# 3_cyber60-smk_mcu.net
KiCad netlist of a schematic drawn in Altium Designer
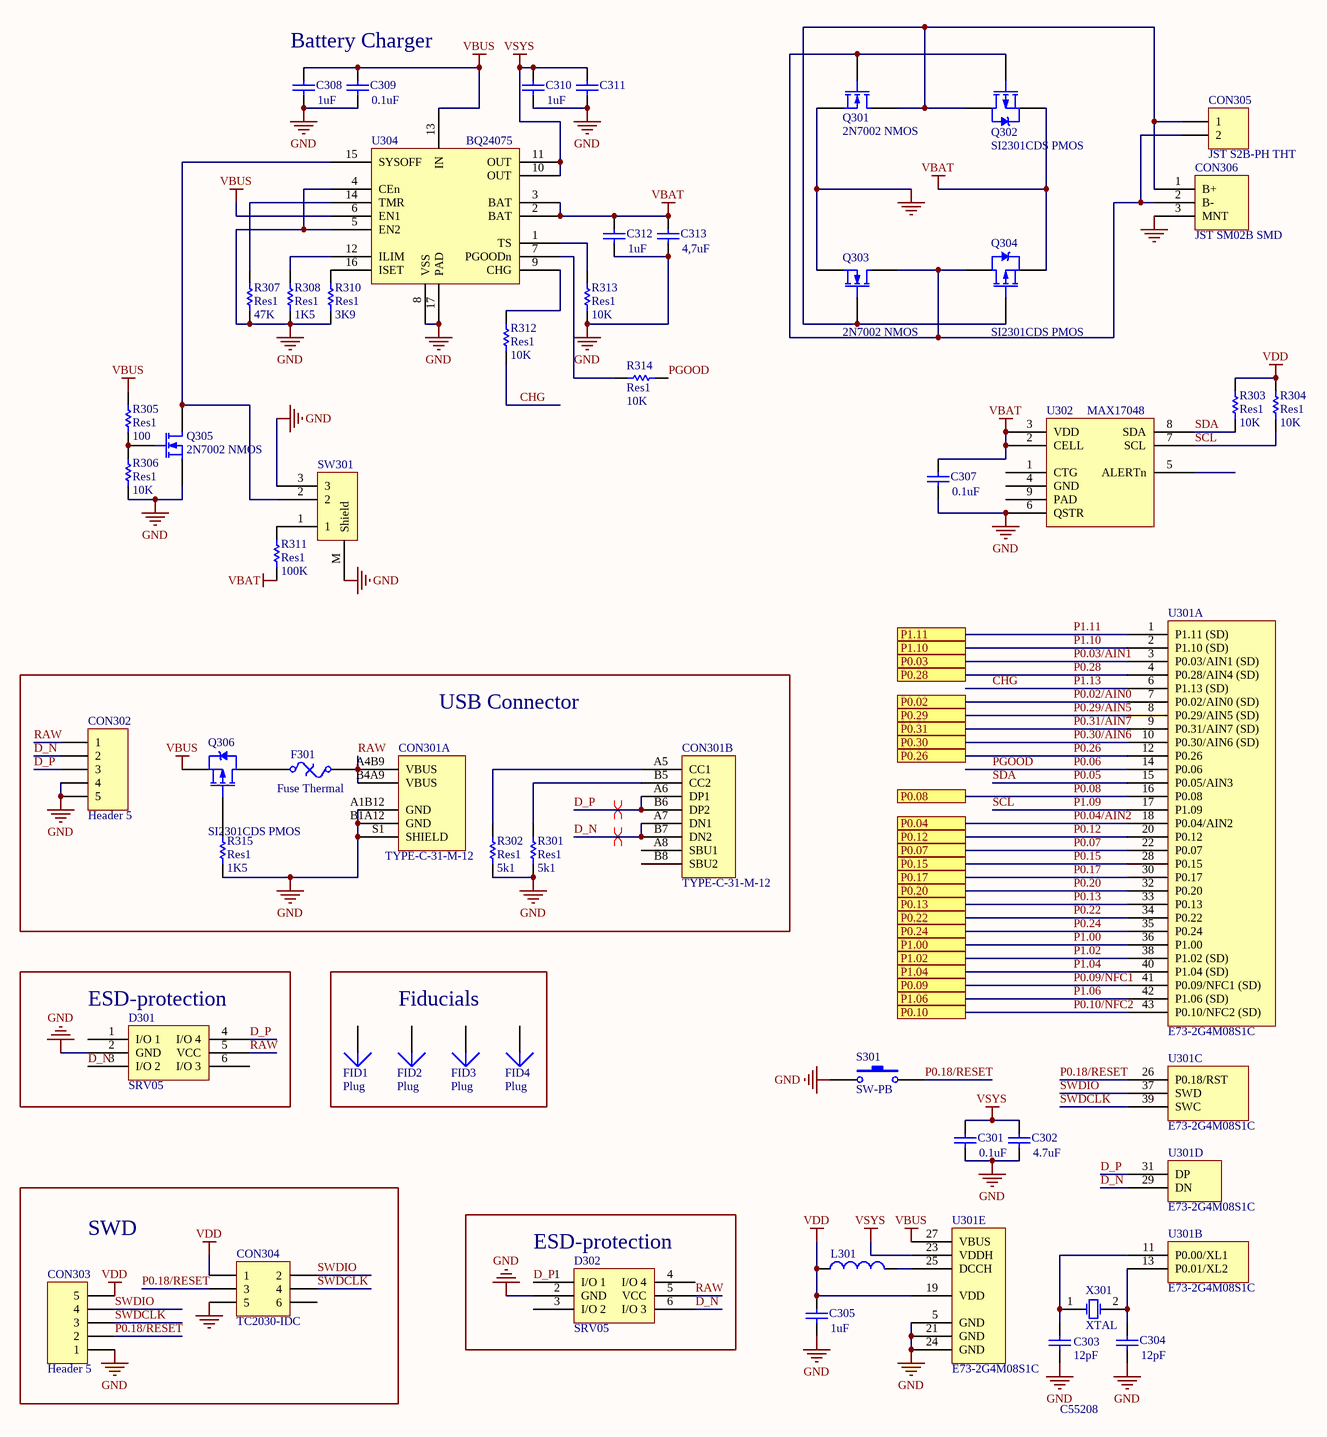
[diagram p0: 3_cyber60-smk_mcu.SchDoc]

(export (version "E")
  (design (tool "Eeschema 10.0.6"))
  (components
    (comp (ref "C301")
      (value "0.1uF")
      (footprint "C0603[1608]")
      (description "Capacitor")
      (fields (field (name "LCSC PART #") "C14663") (field (name "MRF.PART") "CC0603KRX7R9BB104"))
      (libsource (lib "Miscellaneous Devices") (part "Cap"))
    )
    (comp (ref "C302")
      (value "4.7uF")
      (footprint "C0603[1608]")
      (description "Capacitor")
      (fields (field (name "LCSC PART #") "C19666") (field (name "MRF.PART") "CL10A475KO8NNNC"))
      (libsource (lib "Miscellaneous Devices") (part "Cap"))
    )
    (comp (ref "C303")
      (value "12pF")
      (footprint "C0402[1005]")
      (description "Capacitor")
      (fields (field (name "LCSC PART #") "C1547") (field (name "MRF.PART") "0402CG120J500NT"))
      (libsource (lib "Miscellaneous Devices") (part "Cap"))
    )
    (comp (ref "C304")
      (value "12pF")
      (footprint "C0402[1005]")
      (description "Capacitor")
      (fields (field (name "LCSC PART #") "C1547") (field (name "MRF.PART") "0402CG120J500NT"))
      (libsource (lib "Miscellaneous Devices") (part "Cap"))
    )
    (comp (ref "C305")
      (value "1uF")
      (footprint "C0603[1608]")
      (description "Capacitor")
      (fields (field (name "LCSC PART #") "C15849") (field (name "MRF.PART") "CL10A105KB8NNNC"))
      (libsource (lib "Miscellaneous Devices") (part "Cap"))
    )
    (comp (ref "C307")
      (value "0.1uF")
      (footprint "C0603[1608]")
      (description "Capacitor")
      (fields (field (name "LCSC PART #") "C14663") (field (name "MRF.PART") "CC0603KRX7R9BB104"))
      (libsource (lib "Miscellaneous Devices") (part "Cap"))
    )
    (comp (ref "C308")
      (value "1uF")
      (footprint "C0603[1608]")
      (description "Capacitor")
      (fields (field (name "LCSC PART #") "C15849") (field (name "MRF.PART") "CL10A105KB8NNNC"))
      (libsource (lib "Miscellaneous Devices") (part "Cap"))
    )
    (comp (ref "C309")
      (value "0.1uF")
      (footprint "C0603[1608]")
      (description "Capacitor")
      (fields (field (name "LCSC PART #") "C14663") (field (name "MRF.PART") "CC0603KRX7R9BB104"))
      (libsource (lib "Miscellaneous Devices") (part "Cap"))
    )
    (comp (ref "C310")
      (value "1uF")
      (footprint "C0603[1608]")
      (description "Capacitor")
      (fields (field (name "LCSC PART #") "C15849") (field (name "MRF.PART") "CL10A105KB8NNNC"))
      (libsource (lib "Miscellaneous Devices") (part "Cap"))
    )
    (comp (ref "C311")
      (value "~")
      (footprint "C0603[1608]")
      (description "Capacitor")
      (fields (field (name "LCSC PART #") "C19666") (field (name "MRF.PART") "CL10A475KO8NNNC"))
      (libsource (lib "Miscellaneous Devices") (part "Cap"))
    )
    (comp (ref "C312")
      (value "1uF")
      (footprint "C0603[1608]")
      (description "Capacitor")
      (fields (field (name "LCSC PART #") "C15849") (field (name "MRF.PART") "CL10A105KB8NNNC"))
      (libsource (lib "Miscellaneous Devices") (part "Cap"))
    )
    (comp (ref "C313")
      (value "4,7uF")
      (footprint "C0603[1608]")
      (description "Capacitor")
      (fields (field (name "LCSC PART #") "C19666") (field (name "MRF.PART") "CL10A475KO8NNNC"))
      (libsource (lib "Miscellaneous Devices") (part "Cap"))
    )
    (comp (ref "CON301")
      (value "TYPE-C-31-M-12")
      (footprint "TYPE-C-31-M-12")
      (fields (field (name "MFG") "Korean Hroparts Elec") (field (name "LCSC PART #") "C165948"))
      (libsource (lib "Schlib1") (part "TYPE-C-31-M-12"))
    )
    (comp (ref "CON302")
      (value "Header 5")
      (footprint "UDB_COMBO_JST_MOLEX")
      (description "JST for USB daughter board")
      (fields (field (name "MFG") "JST Sales America Inc.") (field (name "LCSC PART #") "C160404"))
      (libsource (lib "") (part "Header 5_1"))
    )
    (comp (ref "CON303")
      (value "Header 5")
      (footprint "HDR1X5")
      (description "Header, 5-Pin")
      (libsource (lib "Miscellaneous Connectors") (part "Header 5"))
    )
    (comp (ref "CON304")
      (value "TC2030-IDC")
      (footprint "TC2030-IDC-NL")
      (description "Header, 3-Pin, Dual row")
      (libsource (lib "Miscellaneous Connectors") (part "Header 3X2"))
    )
    (comp (ref "CON305")
      (value "JST S2B-PH THT")
      (footprint "Keebs:JST S2B-PH-K(LF)(SN)")
      (description "Header, 2-Pin")
      (fields (field (name "LCSC PART #") "C265016") (field (name "MRF.PART") "S2B-PH-K(LF)(SN)"))
      (libsource (lib "Miscellaneous Connectors") (part "Header 2"))
    )
    (comp (ref "CON306")
      (value "JST SM02B SMD")
      (footprint "JST SM02B-SRSS-TB")
      (fields (field (name "LCSC PART #") "C160402") (field (name "MRF.PART") "SM02B-SRSS-TB(LF)(SN)"))
      (libsource (lib "Keebs") (part "JST S2B-PH-SM4-TB"))
    )
    (comp (ref "D301")
      (value "SRV05")
      (footprint "SOT-23-6")
      (fields (field (name "LCSC PART #") "C85364") (field (name "MRF.PART") "SRV05-4-P-T7"))
      (libsource (lib "Keebs") (part "SRV05"))
    )
    (comp (ref "D302")
      (value "SRV05")
      (footprint "SOT-23-6")
      (fields (field (name "LCSC PART #") "C85364") (field (name "MRF.PART") "SRV05-4-P-T7"))
      (libsource (lib "Keebs") (part "SRV05"))
    )
    (comp (ref "F301")
      (value "Fuse Thermal")
      (footprint "C1206[3216]")
      (description "Thermal Fuse")
      (fields (field (name "MFG") "Bel Fuse Inc.") (field (name "LCSC PART #") "C135338"))
      (libsource (lib "Miscellaneous Devices") (part "Fuse Thermal"))
    )
    (comp (ref "FID1")
      (value "Plug")
      (footprint "Fiducial_Nordic")
      (libsource (lib "Miscellaneous Connectors") (part "Plug"))
    )
    (comp (ref "FID2")
      (value "Plug")
      (footprint "Fiducial_Nordic")
      (libsource (lib "Miscellaneous Connectors") (part "Plug"))
    )
    (comp (ref "FID3")
      (value "Plug")
      (footprint "Fiducial_Nordic")
      (libsource (lib "Miscellaneous Connectors") (part "Plug"))
    )
    (comp (ref "FID4")
      (value "Plug")
      (footprint "Fiducial_Nordic")
      (libsource (lib "Miscellaneous Connectors") (part "Plug"))
    )
    (comp (ref "L301")
      (value "Inductor")
      (footprint "L0603[1608]")
      (fields (field (name "LCSC PART #") "C92982") (field (name "MRF.PART") "CBMF1608T100K"))
      (libsource (lib "Simulation Generic Components") (part "Inductor"))
    )
    (comp (ref "Q301")
      (value "2N7002 NMOS")
      (footprint "SOT-23-3")
      (description "N-Channel MOSFET")
      (fields (field (name "LCSC PART #") "C8545") (field (name "MRF.PART") "2N7002"))
      (libsource (lib "Miscellaneous Devices") (part "MOSFET-N"))
    )
    (comp (ref "Q302")
      (value "SI2301CDS PMOS")
      (footprint "SOT-23-3")
      (description "P-Channel Power MOSFET")
      (fields (field (name "MRF.PART") "SI2301CDS-T1-GE3") (field (name "LCSC PART #") "C10487"))
      (libsource (lib "Miscellaneous Devices") (part "PMOS-2"))
    )
    (comp (ref "Q303")
      (value "2N7002 NMOS")
      (footprint "SOT-23-3")
      (description "N-Channel MOSFET")
      (fields (field (name "LCSC PART #") "C8545") (field (name "MRF.PART") "2N7002"))
      (libsource (lib "Miscellaneous Devices") (part "MOSFET-N"))
    )
    (comp (ref "Q304")
      (value "SI2301CDS PMOS")
      (footprint "SOT-23-3")
      (description "P-Channel Power MOSFET")
      (fields (field (name "MRF.PART") "SI2301CDS-T1-GE3") (field (name "LCSC PART #") "C10487"))
      (libsource (lib "Miscellaneous Devices") (part "PMOS-2"))
    )
    (comp (ref "Q305")
      (value "2N7002 NMOS")
      (footprint "SOT-23-3")
      (description "N-Channel MOSFET")
      (fields (field (name "LCSC PART #") "C8545") (field (name "MRF.PART") "2N7002"))
      (libsource (lib "Miscellaneous Devices") (part "MOSFET-N"))
    )
    (comp (ref "Q306")
      (value "SI2301CDS PMOS")
      (footprint "SOT-23-3")
      (description "P-Channel Power MOSFET")
      (fields (field (name "MRF.PART") "SI2301CDS-T1-GE3") (field (name "LCSC PART #") "C10487"))
      (libsource (lib "Miscellaneous Devices") (part "PMOS-2"))
    )
    (comp (ref "R301")
      (value "Res1")
      (footprint "R0603[1608]")
      (description "Resistor")
      (fields
        (field (name "ALTIUM_VALUE") "5k1")
        (field (name "MFG") "Panasonic Electronic Components")
        (field (name "LCSC PART #") "C23186")
      )
      (libsource (lib "Miscellaneous Devices") (part "Res1"))
    )
    (comp (ref "R302")
      (value "Res1")
      (footprint "R0603[1608]")
      (description "Resistor")
      (fields
        (field (name "ALTIUM_VALUE") "5k1")
        (field (name "MFG") "Panasonic Electronic Components")
        (field (name "LCSC PART #") "C23186")
      )
      (libsource (lib "Miscellaneous Devices") (part "Res1"))
    )
    (comp (ref "R303")
      (value "Res1")
      (footprint "R0603[1608]")
      (description "Resistor")
      (fields
        (field (name "ALTIUM_VALUE") "10K")
        (field (name "LCSC PART #") "C25804")
        (field (name "MRF.PART") "0603WAF1002T5E")
      )
      (libsource (lib "Miscellaneous Devices") (part "Res1"))
    )
    (comp (ref "R304")
      (value "Res1")
      (footprint "R0603[1608]")
      (description "Resistor")
      (fields
        (field (name "ALTIUM_VALUE") "10K")
        (field (name "LCSC PART #") "C25804")
        (field (name "MRF.PART") "0603WAF1002T5E")
      )
      (libsource (lib "Miscellaneous Devices") (part "Res1"))
    )
    (comp (ref "R305")
      (value "Res1")
      (footprint "R0603[1608]")
      (description "Resistor")
      (fields
        (field (name "ALTIUM_VALUE") "100")
        (field (name "LCSC PART #") "C22775")
        (field (name "MRF.PART") "0603WAF1000T5E")
      )
      (libsource (lib "Miscellaneous Devices") (part "Res1"))
    )
    (comp (ref "R306")
      (value "Res1")
      (footprint "R0603[1608]")
      (description "Resistor")
      (fields
        (field (name "ALTIUM_VALUE") "10K")
        (field (name "LCSC PART #") "C25804")
        (field (name "MRF.PART") "0603WAF1002T5E")
      )
      (libsource (lib "Miscellaneous Devices") (part "Res1"))
    )
    (comp (ref "R307")
      (value "Res1")
      (footprint "R0603[1608]")
      (description "Resistor")
      (fields
        (field (name "ALTIUM_VALUE") "47K")
        (field (name "LCSC PART #") "C25819")
        (field (name "MRF.PART") "0603WAF4702T5E")
      )
      (libsource (lib "Miscellaneous Devices") (part "Res1"))
    )
    (comp (ref "R308")
      (value "Res1")
      (footprint "R0603[1608]")
      (description "Resistor")
      (fields
        (field (name "ALTIUM_VALUE") "1K5")
        (field (name "LCSC PART #") "C22843")
        (field (name "MRF.PART") "0603WAF1501T5E")
      )
      (libsource (lib "Miscellaneous Devices") (part "Res1"))
    )
    (comp (ref "R310")
      (value "Res1")
      (footprint "R0603[1608]")
      (description "Resistor")
      (fields
        (field (name "ALTIUM_VALUE") "3K9")
        (field (name "LCSC PART #") "C23018")
        (field (name "MRF.PART") "0603WAF3901T5E")
      )
      (libsource (lib "Miscellaneous Devices") (part "Res1"))
    )
    (comp (ref "R311")
      (value "Res1")
      (footprint "R0603[1608]")
      (description "Resistor")
      (fields
        (field (name "ALTIUM_VALUE") "100K")
        (field (name "LCSC PART #") "C25804")
        (field (name "MRF.PART") "0603WAF1002T5E")
      )
      (libsource (lib "Miscellaneous Devices") (part "Res1"))
    )
    (comp (ref "R312")
      (value "Res1")
      (footprint "R0603[1608]")
      (description "Resistor")
      (fields
        (field (name "ALTIUM_VALUE") "10K")
        (field (name "LCSC PART #") "C25804")
        (field (name "MRF.PART") "0603WAF1002T5E")
      )
      (libsource (lib "Miscellaneous Devices") (part "Res1"))
    )
    (comp (ref "R313")
      (value "Res1")
      (footprint "R0603[1608]")
      (description "Resistor")
      (fields
        (field (name "ALTIUM_VALUE") "10K")
        (field (name "LCSC PART #") "C25804")
        (field (name "MRF.PART") "0603WAF1002T5E")
      )
      (libsource (lib "Miscellaneous Devices") (part "Res1"))
    )
    (comp (ref "R314")
      (value "Res1")
      (footprint "R0603[1608]")
      (description "Resistor")
      (fields
        (field (name "ALTIUM_VALUE") "10K")
        (field (name "LCSC PART #") "C25804")
        (field (name "MRF.PART") "0603WAF1002T5E")
      )
      (libsource (lib "Miscellaneous Devices") (part "Res1"))
    )
    (comp (ref "R315")
      (value "Res1")
      (footprint "R0603[1608]")
      (description "Resistor")
      (fields
        (field (name "ALTIUM_VALUE") "1K5")
        (field (name "LCSC PART #") "C22843")
        (field (name "MRF.PART") "0603WAF1501T5E")
      )
      (libsource (lib "Miscellaneous Devices") (part "Res1"))
    )
    (comp (ref "S301")
      (value "SW-PB")
      (footprint "XKB Switch")
      (description "Switch")
      (fields (field (name "MRF.PART") "TS-1187A-C-D-B") (field (name "LCSC PART #") "C318888"))
      (libsource (lib "Miscellaneous Devices") (part "SW-PB"))
    )
    (comp (ref "SW301")
      (value "Korean Hroparts Elec K3-1296S-E2")
      (footprint "Korean Hroparts Elec K3-1296S-E2")
      (fields (field (name "LCSC PART #") "C136659"))
      (libsource (lib "Keebs") (part "Korean Hroparts Elec K3-1296S-E2"))
    )
    (comp (ref "U301")
      (value "E73-2G4M08S1C")
      (footprint "E73-2G4M08S1C")
      (fields (field (name "LCSC PART #") "C356849"))
      (libsource (lib "Keebs") (part "E73-2G4M08S1C"))
    )
    (comp (ref "U302")
      (value "MAX17048")
      (footprint "8TDFN")
      (fields (field (name "LCSC PART #") "C2682616") (field (name "MRF.PART") "MAX17048G+T10"))
      (libsource (lib "Keebs") (part "MAX17048"))
    )
    (comp (ref "U304")
      (value "BQ24075")
      (footprint "QFN16")
      (fields (field (name "LCSC PART #") "C15464") (field (name "MRF.PART") "BQ24075RGTR"))
      (libsource (lib "Keebs") (part "BQ24075"))
    )
    (comp (ref "X301")
      (value "XTAL")
      (footprint "XTAL-2012")
      (description "Crystal Oscillator")
      (fields (field (name "LCSC PART #") "C55208") (field (name "MRF.PART") "X1A0000610002"))
      (libsource (lib "Miscellaneous Devices") (part "XTAL"))
    )
  )
  (nets
    (net (code "1") (name "/CHG") (class "Default")
      (node (ref "R312") (pin "2") (pinfunction "2_2") (pintype "passive"))
      (node (ref "U301") (pin "6") (pinfunction "P1.13_(SD)_6") (pintype "passive"))
    )
    (net (code "2") (name "/D_N") (class "Default")
      (node (ref "CON301") (pin "A7") (pinfunction "DN1_A7") (pintype "passive"))
      (node (ref "CON301") (pin "B7") (pinfunction "DN2_B7") (pintype "passive"))
      (node (ref "CON302") (pin "2") (pinfunction "2_2") (pintype "passive"))
      (node (ref "D301") (pin "3") (pinfunction "I/O_2_3") (pintype "passive"))
      (node (ref "D302") (pin "6") (pinfunction "I/O_3_6") (pintype "passive"))
      (node (ref "U301") (pin "29") (pinfunction "DN_29") (pintype "passive"))
    )
    (net (code "3") (name "/D_P") (class "Default")
      (node (ref "CON301") (pin "A6") (pinfunction "DP1_A6") (pintype "passive"))
      (node (ref "CON301") (pin "B6") (pinfunction "DP2_B6") (pintype "passive"))
      (node (ref "CON302") (pin "3") (pinfunction "3_3") (pintype "passive"))
      (node (ref "D301") (pin "4") (pinfunction "I/O_4_4") (pintype "passive"))
      (node (ref "D302") (pin "1") (pinfunction "I/O_1_1") (pintype "passive"))
      (node (ref "U301") (pin "31") (pinfunction "DP_31") (pintype "passive"))
    )
    (net (code "4") (name "/P0.02{slash}AIN0") (class "Default")
      (node (ref "U301") (pin "7") (pinfunction "P0.02/AIN0_(SD)_7") (pintype "passive"))
    )
    (net (code "5") (name "/P0.03{slash}AIN1") (class "Default")
      (node (ref "U301") (pin "3") (pinfunction "P0.03/AIN1_(SD)_3") (pintype "passive"))
    )
    (net (code "6") (name "/P0.04{slash}AIN2") (class "Default")
      (node (ref "U301") (pin "18") (pinfunction "P0.04/AIN2_18") (pintype "passive"))
    )
    (net (code "7") (name "/P0.05") (class "Default")
      (node (ref "R303") (pin "2") (pinfunction "2_2") (pintype "passive"))
      (node (ref "U301") (pin "15") (pinfunction "P0.05/AIN3_15") (pintype "passive"))
      (node (ref "U302") (pin "8") (pinfunction "SDA_8") (pintype "passive"))
    )
    (net (code "8") (name "/P0.06") (class "Default")
      (node (ref "R314") (pin "2") (pinfunction "2_2") (pintype "passive"))
      (node (ref "U301") (pin "14") (pinfunction "P0.06_14") (pintype "passive"))
    )
    (net (code "9") (name "/P0.07") (class "Default")
      (node (ref "U301") (pin "22") (pinfunction "P0.07_22") (pintype "passive"))
    )
    (net (code "10") (name "/P0.08") (class "Default")
      (node (ref "U301") (pin "16") (pinfunction "P0.08_16") (pintype "passive"))
    )
    (net (code "11") (name "/P0.09{slash}NFC1") (class "Default")
      (node (ref "U301") (pin "41") (pinfunction "P0.09/NFC1_(SD)_41") (pintype "passive"))
    )
    (net (code "12") (name "/P0.10{slash}NFC2") (class "Default")
      (node (ref "U301") (pin "43") (pinfunction "P0.10/NFC2_(SD)_43") (pintype "passive"))
    )
    (net (code "13") (name "/P0.12") (class "Default")
      (node (ref "U301") (pin "20") (pinfunction "P0.12_20") (pintype "passive"))
    )
    (net (code "14") (name "/P0.13") (class "Default")
      (node (ref "U301") (pin "33") (pinfunction "P0.13_33") (pintype "passive"))
    )
    (net (code "15") (name "/P0.15") (class "Default")
      (node (ref "U301") (pin "28") (pinfunction "P0.15_28") (pintype "passive"))
    )
    (net (code "16") (name "/P0.17") (class "Default")
      (node (ref "U301") (pin "30") (pinfunction "P0.17_30") (pintype "passive"))
    )
    (net (code "17") (name "/P0.18{slash}RESET") (class "Default")
      (node (ref "CON303") (pin "2") (pinfunction "2_2") (pintype "passive"))
      (node (ref "CON304") (pin "3") (pinfunction "3_3") (pintype "passive"))
      (node (ref "S301") (pin "2") (pinfunction "2_2") (pintype "passive"))
      (node (ref "U301") (pin "26") (pinfunction "P0.18/RST_26") (pintype "passive"))
    )
    (net (code "18") (name "/P0.20") (class "Default")
      (node (ref "U301") (pin "32") (pinfunction "P0.20_32") (pintype "passive"))
    )
    (net (code "19") (name "/P0.22") (class "Default")
      (node (ref "U301") (pin "34") (pinfunction "P0.22_34") (pintype "passive"))
    )
    (net (code "20") (name "/P0.24") (class "Default")
      (node (ref "U301") (pin "35") (pinfunction "P0.24_35") (pintype "passive"))
    )
    (net (code "21") (name "/P0.26") (class "Default")
      (node (ref "U301") (pin "12") (pinfunction "P0.26_12") (pintype "passive"))
    )
    (net (code "22") (name "/P0.28") (class "Default")
      (node (ref "U301") (pin "4") (pinfunction "P0.28/AIN4_(SD)_4") (pintype "passive"))
    )
    (net (code "23") (name "/P0.29{slash}AIN5") (class "Default")
      (node (ref "U301") (pin "8") (pinfunction "P0.29/AIN5_(SD)_8") (pintype "passive"))
    )
    (net (code "24") (name "/P0.30{slash}AIN6") (class "Default")
      (node (ref "U301") (pin "10") (pinfunction "P0.30/AIN6_(SD)_10") (pintype "passive"))
    )
    (net (code "25") (name "/P0.31{slash}AIN7") (class "Default")
      (node (ref "U301") (pin "9") (pinfunction "P0.31/AIN7_(SD)_9") (pintype "passive"))
    )
    (net (code "26") (name "/P1.00") (class "Default")
      (node (ref "U301") (pin "36") (pinfunction "P1.00_36") (pintype "passive"))
    )
    (net (code "27") (name "/P1.02") (class "Default")
      (node (ref "U301") (pin "38") (pinfunction "P1.02_(SD)_38") (pintype "passive"))
    )
    (net (code "28") (name "/P1.04") (class "Default")
      (node (ref "U301") (pin "40") (pinfunction "P1.04_(SD)_40") (pintype "passive"))
    )
    (net (code "29") (name "/P1.06") (class "Default")
      (node (ref "U301") (pin "42") (pinfunction "P1.06_(SD)_42") (pintype "passive"))
    )
    (net (code "30") (name "/P1.09") (class "Default")
      (node (ref "R304") (pin "2") (pinfunction "2_2") (pintype "passive"))
      (node (ref "U301") (pin "17") (pinfunction "P1.09_17") (pintype "passive"))
      (node (ref "U302") (pin "7") (pinfunction "SCL_7") (pintype "passive"))
    )
    (net (code "31") (name "/P1.10") (class "Default")
      (node (ref "U301") (pin "2") (pinfunction "P1.10_(SD)_2") (pintype "passive"))
    )
    (net (code "32") (name "/P1.11") (class "Default")
      (node (ref "U301") (pin "1") (pinfunction "P1.11_(SD)_1") (pintype "passive"))
    )
    (net (code "33") (name "/RAW") (class "Default")
      (node (ref "CON301") (pin "A4B9") (pinfunction "VBUS_A4B9") (pintype "passive"))
      (node (ref "CON301") (pin "B4A9") (pinfunction "VBUS_B4A9") (pintype "passive"))
      (node (ref "CON302") (pin "1") (pinfunction "1_1") (pintype "passive"))
      (node (ref "D301") (pin "5") (pinfunction "VCC_5") (pintype "passive"))
      (node (ref "D302") (pin "5") (pinfunction "VCC_5") (pintype "passive"))
      (node (ref "F301") (pin "2") (pinfunction "2_2") (pintype "passive"))
    )
    (net (code "34") (name "/SWDCLK") (class "Default")
      (node (ref "CON303") (pin "3") (pinfunction "3_3") (pintype "passive"))
      (node (ref "CON304") (pin "4") (pinfunction "4_4") (pintype "passive"))
      (node (ref "U301") (pin "39") (pinfunction "SWC_39") (pintype "passive"))
    )
    (net (code "35") (name "/SWDIO") (class "Default")
      (node (ref "CON303") (pin "4") (pinfunction "4_4") (pintype "passive"))
      (node (ref "CON304") (pin "2") (pinfunction "2_2") (pintype "passive"))
      (node (ref "U301") (pin "37") (pinfunction "SWD_37") (pintype "passive"))
    )
    (net (code "36") (name "GND") (class "Default")
      (node (ref "C301") (pin "1") (pinfunction "1_1") (pintype "passive"))
      (node (ref "C302") (pin "1") (pinfunction "1_1") (pintype "passive"))
      (node (ref "C303") (pin "1") (pinfunction "1_1") (pintype "passive"))
      (node (ref "C304") (pin "1") (pinfunction "1_1") (pintype "passive"))
      (node (ref "C305") (pin "1") (pinfunction "1_1") (pintype "passive"))
      (node (ref "C307") (pin "1") (pinfunction "1_1") (pintype "passive"))
      (node (ref "C308") (pin "1") (pinfunction "1_1") (pintype "passive"))
      (node (ref "C309") (pin "1") (pinfunction "1_1") (pintype "passive"))
      (node (ref "C310") (pin "1") (pinfunction "1_1") (pintype "passive"))
      (node (ref "C311") (pin "1") (pinfunction "1_1") (pintype "passive"))
      (node (ref "C312") (pin "1") (pinfunction "1_1") (pintype "passive"))
      (node (ref "C313") (pin "1") (pinfunction "1_1") (pintype "passive"))
      (node (ref "CON301") (pin "A1B12") (pinfunction "GND_A1B12") (pintype "passive"))
      (node (ref "CON301") (pin "B1A12") (pinfunction "GND_B1A12") (pintype "passive"))
      (node (ref "CON301") (pin "S1") (pinfunction "SHIELD_S1") (pintype "passive"))
      (node (ref "CON302") (pin "4") (pinfunction "4_4") (pintype "passive"))
      (node (ref "CON302") (pin "5") (pinfunction "5_5") (pintype "passive"))
      (node (ref "CON303") (pin "1") (pinfunction "1_1") (pintype "passive"))
      (node (ref "CON304") (pin "5") (pinfunction "5_5") (pintype "passive"))
      (node (ref "CON306") (pin "3") (pinfunction "MNT_3") (pintype "passive"))
      (node (ref "D301") (pin "2") (pinfunction "GND_2") (pintype "passive"))
      (node (ref "D302") (pin "2") (pinfunction "GND_2") (pintype "passive"))
      (node (ref "Q301") (pin "2") (pinfunction "S_2") (pintype "passive"))
      (node (ref "Q303") (pin "2") (pinfunction "S_2") (pintype "passive"))
      (node (ref "Q305") (pin "2") (pinfunction "S_2") (pintype "passive"))
      (node (ref "R301") (pin "2") (pinfunction "2_2") (pintype "passive"))
      (node (ref "R302") (pin "2") (pinfunction "2_2") (pintype "passive"))
      (node (ref "R306") (pin "2") (pinfunction "2_2") (pintype "passive"))
      (node (ref "R307") (pin "2") (pinfunction "2_2") (pintype "passive"))
      (node (ref "R308") (pin "2") (pinfunction "2_2") (pintype "passive"))
      (node (ref "R310") (pin "2") (pinfunction "2_2") (pintype "passive"))
      (node (ref "R313") (pin "2") (pinfunction "2_2") (pintype "passive"))
      (node (ref "R315") (pin "2") (pinfunction "2_2") (pintype "passive"))
      (node (ref "S301") (pin "1") (pinfunction "1_1") (pintype "passive"))
      (node (ref "SW301") (pin "3") (pinfunction "3_3") (pintype "passive"))
      (node (ref "SW301") (pin "M") (pinfunction "Shield_M") (pintype "passive"))
      (node (ref "U301") (pin "21") (pinfunction "GND_21") (pintype "passive"))
      (node (ref "U301") (pin "24") (pinfunction "GND_24") (pintype "passive"))
      (node (ref "U301") (pin "5") (pinfunction "GND_5") (pintype "passive"))
      (node (ref "U302") (pin "6") (pinfunction "QSTR_6") (pintype "passive"))
      (node (ref "U304") (pin "17") (pinfunction "PAD_17") (pintype "passive"))
      (node (ref "U304") (pin "4") (pinfunction "CEn_4") (pintype "passive"))
      (node (ref "U304") (pin "5") (pinfunction "EN2_5") (pintype "passive"))
      (node (ref "U304") (pin "8") (pinfunction "VSS_8") (pintype "passive"))
    )
    (net (code "37") (name "Net-(CON301B-CC1)") (class "Default")
      (node (ref "CON301") (pin "A5") (pinfunction "CC1_A5") (pintype "passive"))
      (node (ref "R302") (pin "1") (pinfunction "1_1") (pintype "passive"))
    )
    (net (code "38") (name "Net-(CON301B-CC2)") (class "Default")
      (node (ref "CON301") (pin "B5") (pinfunction "CC2_B5") (pintype "passive"))
      (node (ref "R301") (pin "1") (pinfunction "1_1") (pintype "passive"))
    )
    (net (code "39") (name "Net-(CON306-B+)") (class "Default")
      (node (ref "CON305") (pin "1") (pinfunction "1_1") (pintype "passive"))
      (node (ref "CON306") (pin "1") (pinfunction "B+_1") (pintype "passive"))
      (node (ref "Q301") (pin "3") (pinfunction "D_3") (pintype "passive"))
      (node (ref "Q302") (pin "3") (pinfunction "D_3") (pintype "passive"))
      (node (ref "Q303") (pin "1") (pinfunction "G_1") (pintype "passive"))
      (node (ref "Q304") (pin "1") (pinfunction "G_1") (pintype "passive"))
    )
    (net (code "40") (name "Net-(CON306-B-)") (class "Default")
      (node (ref "CON305") (pin "2") (pinfunction "2_2") (pintype "passive"))
      (node (ref "CON306") (pin "2") (pinfunction "B-_2") (pintype "passive"))
      (node (ref "Q301") (pin "1") (pinfunction "G_1") (pintype "passive"))
      (node (ref "Q302") (pin "1") (pinfunction "G_1") (pintype "passive"))
      (node (ref "Q303") (pin "3") (pinfunction "D_3") (pintype "passive"))
      (node (ref "Q304") (pin "3") (pinfunction "D_3") (pintype "passive"))
    )
    (net (code "41") (name "Net-(Q305-D)") (class "Default")
      (node (ref "Q305") (pin "3") (pinfunction "D_3") (pintype "passive"))
      (node (ref "SW301") (pin "2") (pinfunction "2_2") (pintype "passive"))
      (node (ref "U304") (pin "15") (pinfunction "SYSOFF_15") (pintype "passive"))
    )
    (net (code "42") (name "Net-(Q305-G)") (class "Default")
      (node (ref "Q305") (pin "1") (pinfunction "G_1") (pintype "passive"))
      (node (ref "R305") (pin "2") (pinfunction "2_2") (pintype "passive"))
      (node (ref "R306") (pin "1") (pinfunction "1_1") (pintype "passive"))
    )
    (net (code "43") (name "Net-(Q306-D)") (class "Default")
      (node (ref "F301") (pin "1") (pinfunction "1_1") (pintype "passive"))
      (node (ref "Q306") (pin "3") (pinfunction "D_3") (pintype "passive"))
    )
    (net (code "44") (name "Net-(Q306-G)") (class "Default")
      (node (ref "Q306") (pin "1") (pinfunction "G_1") (pintype "passive"))
      (node (ref "R315") (pin "1") (pinfunction "1_1") (pintype "passive"))
    )
    (net (code "45") (name "Net-(R311-Pad1)") (class "Default")
      (node (ref "R311") (pin "1") (pinfunction "1_1") (pintype "passive"))
      (node (ref "SW301") (pin "1") (pinfunction "1_1") (pintype "passive"))
    )
    (net (code "46") (name "Net-(U301B-P0.00{slash}XL1)") (class "Default")
      (node (ref "C303") (pin "2") (pinfunction "2_2") (pintype "passive"))
      (node (ref "U301") (pin "11") (pinfunction "P0.00/XL1_11") (pintype "passive"))
      (node (ref "X301") (pin "1") (pinfunction "OSC1_1") (pintype "passive"))
    )
    (net (code "47") (name "Net-(U301B-P0.01{slash}XL2)") (class "Default")
      (node (ref "C304") (pin "2") (pinfunction "2_2") (pintype "passive"))
      (node (ref "U301") (pin "13") (pinfunction "P0.01/XL2_13") (pintype "passive"))
      (node (ref "X301") (pin "2") (pinfunction "OSC2_2") (pintype "passive"))
    )
    (net (code "48") (name "Net-(U301E-DCCH)") (class "Default")
      (node (ref "L301") (pin "2") (pinfunction "2_2") (pintype "passive"))
      (node (ref "U301") (pin "25") (pinfunction "DCCH_25") (pintype "passive"))
    )
    (net (code "49") (name "Net-(U304-CHG)") (class "Default")
      (node (ref "R312") (pin "1") (pinfunction "1_1") (pintype "passive"))
      (node (ref "U304") (pin "9") (pinfunction "CHG_9") (pintype "passive"))
    )
    (net (code "50") (name "Net-(U304-ILIM)") (class "Default")
      (node (ref "R308") (pin "1") (pinfunction "1_1") (pintype "passive"))
      (node (ref "U304") (pin "12") (pinfunction "ILIM_12") (pintype "passive"))
    )
    (net (code "51") (name "Net-(U304-ISET)") (class "Default")
      (node (ref "R310") (pin "1") (pinfunction "1_1") (pintype "passive"))
      (node (ref "U304") (pin "16") (pinfunction "ISET_16") (pintype "passive"))
    )
    (net (code "52") (name "Net-(U304-PGOODn)") (class "Default")
      (node (ref "R314") (pin "1") (pinfunction "1_1") (pintype "passive"))
      (node (ref "U304") (pin "7") (pinfunction "PGOODn_7") (pintype "passive"))
    )
    (net (code "53") (name "Net-(U304-TMR)") (class "Default")
      (node (ref "R307") (pin "1") (pinfunction "1_1") (pintype "passive"))
      (node (ref "U304") (pin "14") (pinfunction "TMR_14") (pintype "passive"))
    )
    (net (code "54") (name "Net-(U304-TS)") (class "Default")
      (node (ref "R313") (pin "1") (pinfunction "1_1") (pintype "passive"))
      (node (ref "U304") (pin "1") (pinfunction "TS_1") (pintype "passive"))
    )
    (net (code "55") (name "VBAT") (class "Default")
      (node (ref "C307") (pin "2") (pinfunction "2_2") (pintype "passive"))
      (node (ref "C312") (pin "2") (pinfunction "2_2") (pintype "passive"))
      (node (ref "C313") (pin "2") (pinfunction "2_2") (pintype "passive"))
      (node (ref "Q302") (pin "2") (pinfunction "S_2") (pintype "passive"))
      (node (ref "Q304") (pin "2") (pinfunction "S_2") (pintype "passive"))
      (node (ref "R311") (pin "2") (pinfunction "2_2") (pintype "passive"))
      (node (ref "U302") (pin "2") (pinfunction "CELL_2") (pintype "passive"))
      (node (ref "U302") (pin "3") (pinfunction "VDD_3") (pintype "passive"))
      (node (ref "U304") (pin "2") (pinfunction "BAT_2") (pintype "passive"))
      (node (ref "U304") (pin "3") (pinfunction "BAT_3") (pintype "passive"))
    )
    (net (code "56") (name "VBUS") (class "Default")
      (node (ref "C308") (pin "2") (pinfunction "2_2") (pintype "passive"))
      (node (ref "C309") (pin "2") (pinfunction "2_2") (pintype "passive"))
      (node (ref "Q306") (pin "2") (pinfunction "S_2") (pintype "passive"))
      (node (ref "R305") (pin "1") (pinfunction "1_1") (pintype "passive"))
      (node (ref "U301") (pin "27") (pinfunction "VBUS_27") (pintype "passive"))
      (node (ref "U304") (pin "13") (pinfunction "IN_13") (pintype "passive"))
      (node (ref "U304") (pin "6") (pinfunction "EN1_6") (pintype "passive"))
    )
    (net (code "57") (name "VDD") (class "Default")
      (node (ref "C305") (pin "2") (pinfunction "2_2") (pintype "passive"))
      (node (ref "CON303") (pin "5") (pinfunction "5_5") (pintype "passive"))
      (node (ref "CON304") (pin "1") (pinfunction "1_1") (pintype "passive"))
      (node (ref "L301") (pin "1") (pinfunction "1_1") (pintype "passive"))
      (node (ref "R303") (pin "1") (pinfunction "1_1") (pintype "passive"))
      (node (ref "R304") (pin "1") (pinfunction "1_1") (pintype "passive"))
      (node (ref "U301") (pin "19") (pinfunction "VDD_19") (pintype "passive"))
    )
    (net (code "58") (name "VSYS") (class "Default")
      (node (ref "C301") (pin "2") (pinfunction "2_2") (pintype "passive"))
      (node (ref "C302") (pin "2") (pinfunction "2_2") (pintype "passive"))
      (node (ref "C310") (pin "2") (pinfunction "2_2") (pintype "passive"))
      (node (ref "C311") (pin "2") (pinfunction "2_2") (pintype "passive"))
      (node (ref "U301") (pin "23") (pinfunction "VDDH_23") (pintype "passive"))
      (node (ref "U304") (pin "10") (pinfunction "OUT_10") (pintype "passive"))
      (node (ref "U304") (pin "11") (pinfunction "OUT_11") (pintype "passive"))
    )
    (net (code "59") (name "unconnected-(CON301B-SBU1-PadA8)") (class "Default")
      (node (ref "CON301") (pin "A8") (pinfunction "SBU1_A8") (pintype "passive"))
    )
    (net (code "60") (name "unconnected-(CON301B-SBU2-PadB8)") (class "Default")
      (node (ref "CON301") (pin "B8") (pinfunction "SBU2_B8") (pintype "passive"))
    )
    (net (code "61") (name "unconnected-(CON304-Pad6)") (class "Default")
      (node (ref "CON304") (pin "6") (pinfunction "6_6") (pintype "passive"))
    )
    (net (code "62") (name "unconnected-(D301-I{slash}O_1-Pad1)") (class "Default")
      (node (ref "D301") (pin "1") (pinfunction "I/O_1_1") (pintype "passive"))
    )
    (net (code "63") (name "unconnected-(D301-I{slash}O_3-Pad6)") (class "Default")
      (node (ref "D301") (pin "6") (pinfunction "I/O_3_6") (pintype "passive"))
    )
    (net (code "64") (name "unconnected-(D302-I{slash}O_2-Pad3)") (class "Default")
      (node (ref "D302") (pin "3") (pinfunction "I/O_2_3") (pintype "passive"))
    )
    (net (code "65") (name "unconnected-(D302-I{slash}O_4-Pad4)") (class "Default")
      (node (ref "D302") (pin "4") (pinfunction "I/O_4_4") (pintype "passive"))
    )
    (net (code "66") (name "unconnected-(FID1-Pad1)") (class "Default")
      (node (ref "FID1") (pin "1") (pinfunction "1_1") (pintype "passive"))
    )
    (net (code "67") (name "unconnected-(FID2-Pad1)") (class "Default")
      (node (ref "FID2") (pin "1") (pinfunction "1_1") (pintype "passive"))
    )
    (net (code "68") (name "unconnected-(FID3-Pad1)") (class "Default")
      (node (ref "FID3") (pin "1") (pinfunction "1_1") (pintype "passive"))
    )
    (net (code "69") (name "unconnected-(FID4-Pad1)") (class "Default")
      (node (ref "FID4") (pin "1") (pinfunction "1_1") (pintype "passive"))
    )
    (net (code "70") (name "unconnected-(U302-ALERTn-Pad5)") (class "Default")
      (node (ref "U302") (pin "5") (pinfunction "ALERTn_5") (pintype "passive"))
    )
    (net (code "71") (name "unconnected-(U302-CTG-Pad1)") (class "Default")
      (node (ref "U302") (pin "1") (pinfunction "CTG_1") (pintype "passive"))
    )
    (net (code "72") (name "unconnected-(U302-GND-Pad4)") (class "Default")
      (node (ref "U302") (pin "4") (pinfunction "GND_4") (pintype "passive"))
    )
    (net (code "73") (name "unconnected-(U302-PAD-Pad9)") (class "Default")
      (node (ref "U302") (pin "9") (pinfunction "PAD_9") (pintype "passive"))
    )
  )
)
